# SCH_esp_charge_normal.net
KiCad netlist of a schematic drawn in EasyEDA
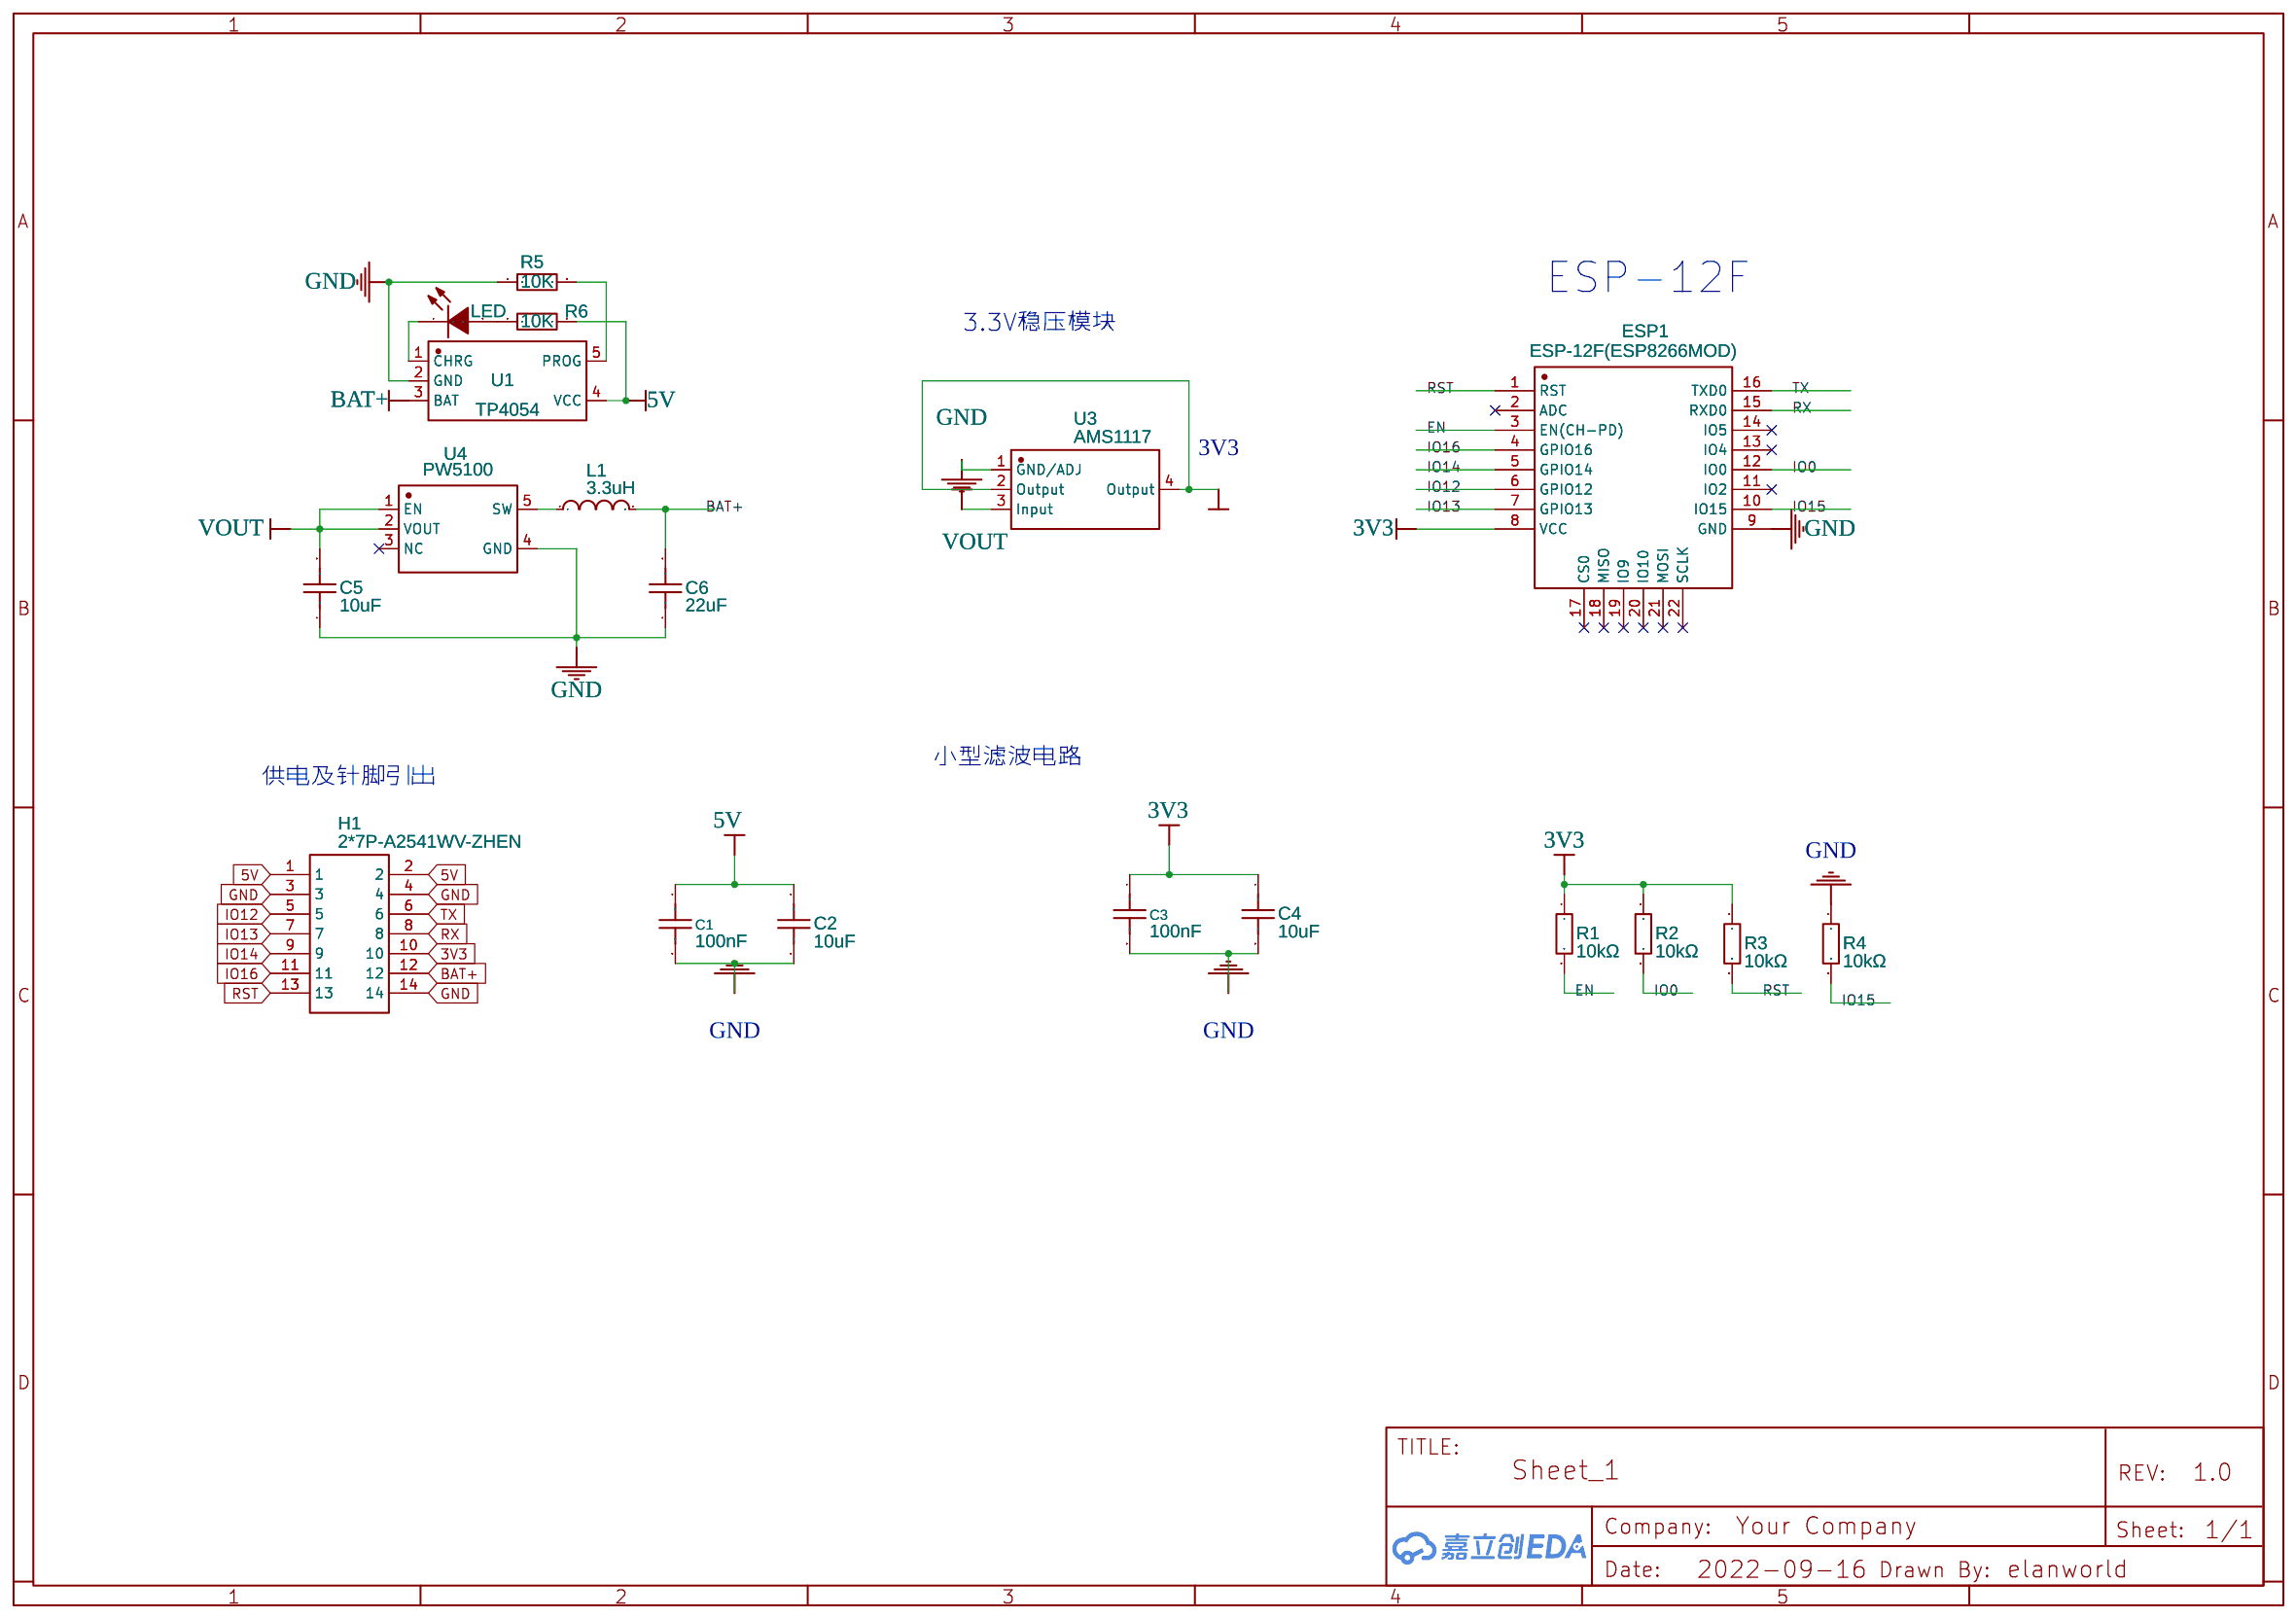
[diagram p0: schematic sheet]

(export (version "E")
  (design (tool "Eeschema 10.0.6"))
  (components
    (comp (ref "C1")
      (value "100nF")
      (fields
        (field (name "BOM_Manufacturer Part") "0805B104K101NT")
        (field (name "BOM_Supplier Part") "C89258")
      )
      (libsource (lib "") (part "0805B104K101NT"))
    )
    (comp (ref "C2")
      (value "10uF")
      (fields
        (field (name "BOM_Manufacturer Part") "C0805X6S106K350NT")
        (field (name "BOM_Supplier Part") "C2844304")
      )
      (libsource (lib "") (part "C0805X6S106K350NT"))
    )
    (comp (ref "C3")
      (value "100nF")
      (fields
        (field (name "BOM_Manufacturer Part") "0805B104K101NT")
        (field (name "BOM_Supplier Part") "C89258")
      )
      (libsource (lib "") (part "0805B104K101NT"))
    )
    (comp (ref "C4")
      (value "10uF")
      (fields
        (field (name "BOM_Manufacturer Part") "C0805X6S106K350NT")
        (field (name "BOM_Supplier Part") "C2844304")
      )
      (libsource (lib "") (part "C0805X6S106K350NT"))
    )
    (comp (ref "C5")
      (value "10uF")
      (fields
        (field (name "BOM_Manufacturer Part") "CL10A106MA8NRNC")
        (field (name "BOM_Supplier Part") "C96446")
      )
      (libsource (lib "") (part "CL10A106MA8NRNC"))
    )
    (comp (ref "C6")
      (value "22uF")
      (fields
        (field (name "BOM_Manufacturer Part") "CL10A226MQ8NRNC")
        (field (name "BOM_Supplier Part") "C59461")
      )
      (libsource (lib "") (part "CL10A226MQ8NRNC"))
    )
    (comp (ref "ESP1")
      (value "ESP-12F(ESP8266MOD)")
      (fields (field (name "BOM_Supplier Part") "C82891"))
      (libsource (lib "") (part "ESP-12F(ESP8266MOD)"))
    )
    (comp (ref "H1")
      (value "2*7P-A2541WV-ZHEN")
      (fields
        (field (name "BOM_Manufacturer Part") "A2541WV-2x7P")
        (field (name "BOM_Supplier Part") "C225522")
      )
      (libsource (lib "") (part "2*7P-A2541WV-ZHEN"))
    )
    (comp (ref "L1")
      (value "3.3uH")
      (fields
        (field (name "BOM_Manufacturer Part") "LVF252A12-3R3M-N")
        (field (name "BOM_Supplier Part") "C142155")
      )
      (libsource (lib "") (part "LVF252A12-3R3M-N"))
    )
    (comp (ref "LED1")
      (value "LED")
      (fields
        (field (name "BOM_Manufacturer Part") "FC-F1005UGK-520M5")
        (field (name "BOM_Supplier Part") "C130723")
      )
      (libsource (lib "") (part "FC-F1005UGK-520M5"))
    )
    (comp (ref "R1")
      (value "10kΩ")
      (fields
        (field (name "BOM_Manufacturer Part") "QR0805F10KP05")
        (field (name "BOM_Supplier Part") "C176201")
      )
      (libsource (lib "") (part "QR0805F10KP05"))
    )
    (comp (ref "R2")
      (value "10kΩ")
      (fields
        (field (name "BOM_Manufacturer Part") "QR0805F10KP05")
        (field (name "BOM_Supplier Part") "C176201")
      )
      (libsource (lib "") (part "QR0805F10KP05"))
    )
    (comp (ref "R3")
      (value "10kΩ")
      (fields
        (field (name "BOM_Manufacturer Part") "QR0805F10KP05")
        (field (name "BOM_Supplier Part") "C176201")
      )
      (libsource (lib "") (part "QR0805F10KP05"))
    )
    (comp (ref "R4")
      (value "10kΩ")
      (fields
        (field (name "BOM_Manufacturer Part") "QR0805F10KP05")
        (field (name "BOM_Supplier Part") "C176201")
      )
      (libsource (lib "") (part "QR0805F10KP05"))
    )
    (comp (ref "R5")
      (value "10K")
      (fields
        (field (name "BOM_Manufacturer Part") "RC0402FR-0710KL")
        (field (name "BOM_Supplier Part") "C25744")
      )
      (libsource (lib "") (part "RC0402FR-0710KL"))
    )
    (comp (ref "R6")
      (value "10K")
      (fields
        (field (name "BOM_Manufacturer Part") "RC0402FR-0710KL")
        (field (name "BOM_Supplier Part") "C25744")
      )
      (libsource (lib "") (part "RC0402FR-0710KL"))
    )
    (comp (ref "U1")
      (value "TP4054")
      (fields (field (name "BOM_Supplier Part") "C32574"))
      (libsource (lib "") (part "TP4054"))
    )
    (comp (ref "U3")
      (value "AMS1117")
      (fields
        (field (name "BOM_Manufacturer Part") "AMS1117-3.3")
        (field (name "BOM_Supplier Part") "C369933")
      )
      (libsource (lib "") (part "AMS1117-3.3_C369933"))
    )
    (comp (ref "U4") (value "PW5100") (libsource (lib "") (part "PW5100")))
  )
  (nets
    (net (code "1") (name "/EN") (class "Default")
      (node (ref "ESP1") (pin "3") (pinfunction "EN(CH-PD)_3") (pintype "unspecified"))
      (node (ref "R1") (pin "2") (pinfunction "2_2") (pintype "unspecified"))
    )
    (net (code "2") (name "/IO0") (class "Default")
      (node (ref "ESP1") (pin "12") (pinfunction "IO0_12") (pintype "unspecified"))
      (node (ref "R2") (pin "2") (pinfunction "2_2") (pintype "unspecified"))
    )
    (net (code "3") (name "/IO15") (class "Default")
      (node (ref "ESP1") (pin "10") (pinfunction "IO15_10") (pintype "unspecified"))
      (node (ref "R4") (pin "2") (pinfunction "2_2") (pintype "unspecified"))
    )
    (net (code "4") (name "3V3") (class "Default")
      (node (ref "C3") (pin "1") (pinfunction "1_1") (pintype "unspecified"))
      (node (ref "C4") (pin "1") (pinfunction "1_1") (pintype "unspecified"))
      (node (ref "ESP1") (pin "8") (pinfunction "VCC_8") (pintype "unspecified"))
      (node (ref "H1") (pin "10") (pinfunction "10_10") (pintype "unspecified"))
      (node (ref "R1") (pin "1") (pinfunction "1_1") (pintype "unspecified"))
      (node (ref "R2") (pin "1") (pinfunction "1_1") (pintype "unspecified"))
      (node (ref "R3") (pin "1") (pinfunction "1_1") (pintype "unspecified"))
      (node (ref "U3") (pin "2") (pinfunction "Output_2") (pintype "unspecified"))
      (node (ref "U3") (pin "4") (pinfunction "Output_4") (pintype "unspecified"))
    )
    (net (code "5") (name "5V") (class "Default")
      (node (ref "C1") (pin "1") (pinfunction "1_1") (pintype "unspecified"))
      (node (ref "C2") (pin "1") (pinfunction "1_1") (pintype "unspecified"))
      (node (ref "H1") (pin "1") (pinfunction "1_1") (pintype "unspecified"))
      (node (ref "H1") (pin "2") (pinfunction "2_2") (pintype "unspecified"))
      (node (ref "R6") (pin "2") (pinfunction "2_2") (pintype "input"))
      (node (ref "U1") (pin "4") (pinfunction "VCC_4") (pintype "unspecified"))
    )
    (net (code "6") (name "BAT+") (class "Default")
      (node (ref "C6") (pin "2") (pinfunction "2_2") (pintype "unspecified"))
      (node (ref "H1") (pin "12") (pinfunction "12_12") (pintype "unspecified"))
      (node (ref "L1") (pin "2") (pinfunction "2_2") (pintype "unspecified"))
      (node (ref "U1") (pin "3") (pinfunction "BAT_3") (pintype "unspecified"))
    )
    (net (code "7") (name "GND") (class "Default")
      (node (ref "C1") (pin "2") (pinfunction "2_2") (pintype "unspecified"))
      (node (ref "C2") (pin "2") (pinfunction "2_2") (pintype "unspecified"))
      (node (ref "C3") (pin "2") (pinfunction "2_2") (pintype "unspecified"))
      (node (ref "C4") (pin "2") (pinfunction "2_2") (pintype "unspecified"))
      (node (ref "C5") (pin "1") (pinfunction "1_1") (pintype "unspecified"))
      (node (ref "C6") (pin "1") (pinfunction "1_1") (pintype "unspecified"))
      (node (ref "ESP1") (pin "9") (pinfunction "GND_9") (pintype "unspecified"))
      (node (ref "H1") (pin "14") (pinfunction "14_14") (pintype "unspecified"))
      (node (ref "H1") (pin "3") (pinfunction "3_3") (pintype "unspecified"))
      (node (ref "H1") (pin "4") (pinfunction "4_4") (pintype "unspecified"))
      (node (ref "R4") (pin "1") (pinfunction "1_1") (pintype "unspecified"))
      (node (ref "R5") (pin "1") (pinfunction "1_1") (pintype "input"))
      (node (ref "U1") (pin "2") (pinfunction "GND_2") (pintype "unspecified"))
      (node (ref "U3") (pin "1") (pinfunction "GND/ADJ_1") (pintype "unspecified"))
      (node (ref "U4") (pin "4") (pinfunction "GND_4") (pintype "unspecified"))
    )
    (net (code "8") (name "IO12") (class "Default")
      (node (ref "ESP1") (pin "6") (pinfunction "GPIO12_6") (pintype "unspecified"))
      (node (ref "H1") (pin "5") (pinfunction "5_5") (pintype "unspecified"))
    )
    (net (code "9") (name "IO13") (class "Default")
      (node (ref "ESP1") (pin "7") (pinfunction "GPIO13_7") (pintype "unspecified"))
      (node (ref "H1") (pin "7") (pinfunction "7_7") (pintype "unspecified"))
    )
    (net (code "10") (name "IO14") (class "Default")
      (node (ref "ESP1") (pin "5") (pinfunction "GPIO14_5") (pintype "unspecified"))
      (node (ref "H1") (pin "9") (pinfunction "9_9") (pintype "unspecified"))
    )
    (net (code "11") (name "IO16") (class "Default")
      (node (ref "ESP1") (pin "4") (pinfunction "GPIO16_4") (pintype "unspecified"))
      (node (ref "H1") (pin "11") (pinfunction "11_11") (pintype "unspecified"))
    )
    (net (code "12") (name "Net-(LED1-A)") (class "Default")
      (node (ref "LED1") (pin "2") (pinfunction "A_2") (pintype "unspecified"))
      (node (ref "R6") (pin "1") (pinfunction "1_1") (pintype "input"))
    )
    (net (code "13") (name "Net-(LED1-K)") (class "Default")
      (node (ref "LED1") (pin "1") (pinfunction "K_1") (pintype "unspecified"))
      (node (ref "U1") (pin "1") (pinfunction "CHRG_1") (pintype "unspecified"))
    )
    (net (code "14") (name "Net-(U1-PROG)") (class "Default")
      (node (ref "R5") (pin "2") (pinfunction "2_2") (pintype "input"))
      (node (ref "U1") (pin "5") (pinfunction "PROG_5") (pintype "unspecified"))
    )
    (net (code "15") (name "Net-(U4-SW)") (class "Default")
      (node (ref "L1") (pin "1") (pinfunction "1_1") (pintype "unspecified"))
      (node (ref "U4") (pin "5") (pinfunction "SW_5") (pintype "unspecified"))
    )
    (net (code "16") (name "RST") (class "Default")
      (node (ref "ESP1") (pin "1") (pinfunction "RST_1") (pintype "unspecified"))
      (node (ref "H1") (pin "13") (pinfunction "13_13") (pintype "unspecified"))
      (node (ref "R3") (pin "2") (pinfunction "2_2") (pintype "unspecified"))
    )
    (net (code "17") (name "RX") (class "Default")
      (node (ref "ESP1") (pin "15") (pinfunction "RXD0_15") (pintype "unspecified"))
      (node (ref "H1") (pin "8") (pinfunction "8_8") (pintype "unspecified"))
    )
    (net (code "18") (name "TX") (class "Default")
      (node (ref "ESP1") (pin "16") (pinfunction "TXD0_16") (pintype "unspecified"))
      (node (ref "H1") (pin "6") (pinfunction "6_6") (pintype "unspecified"))
    )
    (net (code "19") (name "VOUT") (class "Default")
      (node (ref "C5") (pin "2") (pinfunction "2_2") (pintype "unspecified"))
      (node (ref "U3") (pin "3") (pinfunction "Input_3") (pintype "unspecified"))
      (node (ref "U4") (pin "1") (pinfunction "EN_1") (pintype "unspecified"))
      (node (ref "U4") (pin "2") (pinfunction "VOUT_2") (pintype "unspecified"))
    )
    (net (code "20") (name "unconnected-(ESP1-ADC-Pad2)") (class "Default")
      (node (ref "ESP1") (pin "2") (pinfunction "ADC_2") (pintype "unspecified+no_connect"))
    )
    (net (code "21") (name "unconnected-(ESP1-CS0-Pad17)") (class "Default")
      (node (ref "ESP1") (pin "17") (pinfunction "CS0_17") (pintype "unspecified+no_connect"))
    )
    (net (code "22") (name "unconnected-(ESP1-IO2-Pad11)") (class "Default")
      (node (ref "ESP1") (pin "11") (pinfunction "IO2_11") (pintype "unspecified+no_connect"))
    )
    (net (code "23") (name "unconnected-(ESP1-IO4-Pad13)") (class "Default")
      (node (ref "ESP1") (pin "13") (pinfunction "IO4_13") (pintype "unspecified+no_connect"))
    )
    (net (code "24") (name "unconnected-(ESP1-IO5-Pad14)") (class "Default")
      (node (ref "ESP1") (pin "14") (pinfunction "IO5_14") (pintype "unspecified+no_connect"))
    )
    (net (code "25") (name "unconnected-(ESP1-IO9-Pad19)") (class "Default")
      (node (ref "ESP1") (pin "19") (pinfunction "IO9_19") (pintype "unspecified+no_connect"))
    )
    (net (code "26") (name "unconnected-(ESP1-IO10-Pad20)") (class "Default")
      (node (ref "ESP1") (pin "20") (pinfunction "IO10_20") (pintype "unspecified+no_connect"))
    )
    (net (code "27") (name "unconnected-(ESP1-MISO-Pad18)") (class "Default")
      (node (ref "ESP1") (pin "18") (pinfunction "MISO_18") (pintype "unspecified+no_connect"))
    )
    (net (code "28") (name "unconnected-(ESP1-MOSI-Pad21)") (class "Default")
      (node (ref "ESP1") (pin "21") (pinfunction "MOSI_21") (pintype "unspecified+no_connect"))
    )
    (net (code "29") (name "unconnected-(ESP1-SCLK-Pad22)") (class "Default")
      (node (ref "ESP1") (pin "22") (pinfunction "SCLK_22") (pintype "unspecified+no_connect"))
    )
    (net (code "30") (name "unconnected-(U4-NC-Pad3)") (class "Default")
      (node (ref "U4") (pin "3") (pinfunction "NC_3") (pintype "unspecified+no_connect"))
    )
  )
)
